# Sheet2.net
KiCad netlist of a schematic drawn in Altium Designer
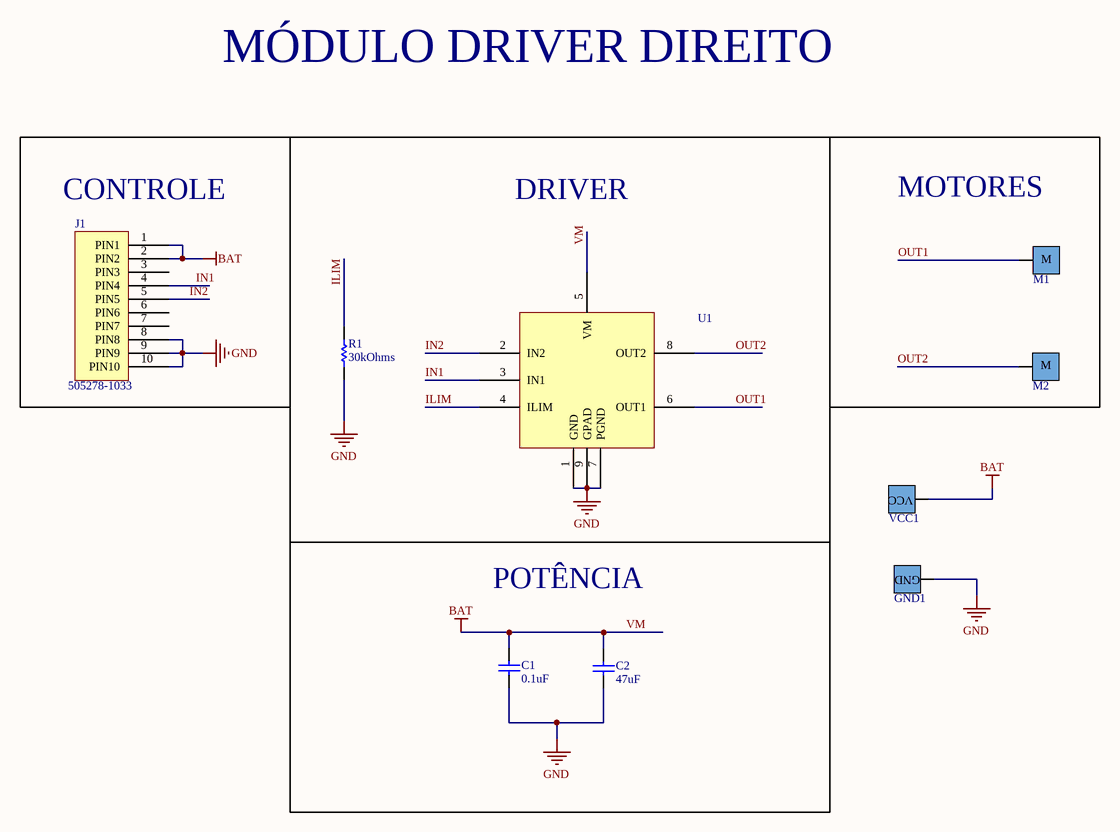
[diagram p0: Sheet2.SchDoc]

(export (version "E")
  (design (tool "Eeschema 10.0.6"))
  (components
    (comp (ref "C1")
      (value "0.1uF")
      (footprint "C0805")
      (description "CAP CER 100nF 25V X7R 0805")
      (fields
        (field (name "MANUFACTURER") "Kemet")
        (field (name "PART NUMBER") "C0805C104M3RACTU")
        (field (name "LIBRARY CONTROL - PERSON THAT CHECKED FOOTPRINT") "Cage")
        (field (name "LIBRARY CONTROL - PERSON THAT CHECKED SCHEMATIC") "Cage")
        (field (name "LIBRARY CONTROL - PERSON THAT DID THE LAST UPDATE FOOTPRINT") "Cage")
        (field (name "LIBRARY CONTROL - PERSON THAT DID THE LAST UPDATE SCHEMATIC") "Cage")
      )
      (libsource (lib "Uai!Tecas") (part "C0805C104M3RACTU"))
    )
    (comp (ref "C2")
      (value "47uF")
      (footprint "C1210")
      (description "CAP CER 47uF 16V X6S 1210")
      (fields
        (field (name "MANUFACTURER") "Murata")
        (field (name "PART NUMBER") "GRM32EC81C476KE15K")
        (field (name "LIBRARY CONTROL - PERSON THAT CHECKED FOOTPRINT") "Cage")
        (field (name "LIBRARY CONTROL - PERSON THAT CHECKED SCHEMATIC") "Cage")
        (field (name "LIBRARY CONTROL - PERSON THAT DID THE LAST UPDATE FOOTPRINT") "Prisma")
        (field (name "LIBRARY CONTROL - PERSON THAT DID THE LAST UPDATE SCHEMATIC") "Prisma")
      )
      (libsource (lib "Capacitor") (part "GRM32EC81C476KE15K"))
    )
    (comp (ref "GND1")
      (value "Ground Pad")
      (footprint "PAD_ALIMENTAÇÃO_MINI")
      (description "GND PAD MINI SUMÔ")
      (libsource (lib "Uai!Tecas") (part "Ground Pad Mini Sumô"))
    )
    (comp (ref "J1")
      (value "505278-1033")
      (footprint "FPC_CON")
      (description "CONN FFC/FPC HORZ 10POS 0.50MM")
      (fields
        (field (name "MANUFACTURER") "Molex")
        (field (name "LIBRARY CONTROL - PERSON THAT CHECKED FOOTPRINT") "Lucas")
        (field (name "LIBRARY CONTROL - PERSON THAT CHECKED SCHEMATIC") "Lucas")
        (field (name "LIBRARY CONTROL - PERSON THAT DID THE LAST UPDATE FOOTPRINT") "Mateus(Dimas)")
        (field (name "LIBRARY CONTROL - PERSON THAT DID THE LAST UPDATE SCHEMATIC") "Mateus(Dimas)")
      )
      (libsource (lib "Uai!Tecas") (part "505278-1033_BODY"))
    )
    (comp (ref "M1")
      (value "Motor Pad")
      (footprint "PAD_MOTOR_MINI")
      (description "MOTOR PAD MINI SUMÔ")
      (libsource (lib "Uai!Tecas") (part "Motor Pad Mini Sumô"))
    )
    (comp (ref "M2")
      (value "Motor Pad")
      (footprint "PAD_MOTOR_MINI")
      (description "MOTOR PAD MINI SUMÔ")
      (libsource (lib "Uai!Tecas") (part "Motor Pad Mini Sumô"))
    )
    (comp (ref "R1")
      (value "30kOhms")
      (footprint "RESC1608X55N")
      (description "RES SMD 30 kOHMS 1% 1/10W 0603")
      (fields
        (field (name "MANUFACTURER") "YAGEO")
        (field (name "PART NUMBER") "RC0603FR-0730KL")
        (field (name "LIBRARY CONTROL - PERSON THAT CHECKED FOOTPRINT") "Guilherme")
        (field (name "LIBRARY CONTROL - PERSON THAT CHECKED SCHEMATIC") "Guilherme")
        (field (name "LIBRARY CONTROL - PERSON THAT DID THE LAST UPDATE FOOTPRINT") "Guilherme")
        (field (name "LIBRARY CONTROL - PERSON THAT DID THE LAST UPDATE SCHEMATIC") "Guilherme")
      )
      (libsource (lib "Uai!Tecas") (part "RC0603FR-0730KL"))
    )
    (comp (ref "U1")
      (value "DRV8871DDA")
      (footprint "SO-PowerPad-8(8_pins)")
      (description "IC MTR DRV (6.5V ~ 45V) (3.5 A) SO-PowerPad-8")
      (fields
        (field (name "MANUFACTURER") "Texas Instruments")
        (field (name "LIBRARY CONTROL - PERSON THAT CHECKED SCHEMATIC") "Stéfany (Ster)")
        (field (name "LIBRARY CONTROL - PERSON THAT CHECKED FOOTPRINT") "Stéfany (Ster)")
        (field (name "LIBRARY CONTROL - PERSON THAT DID THE LAST UPDATE SCHEMATIC") "Stéfany (Ster)")
        (field (name "LIBRARY CONTROL - PERSON THAT DID THE LAST UPDATE FOOTPRINT") "Maria Laura")
      )
      (libsource (lib "Uai!Tecas") (part "DRV8871DDA"))
    )
    (comp (ref "VCC1")
      (value "Source Pad")
      (footprint "PAD_ALIMENTAÇÃO_MINI")
      (description "VCC PAD MINI SUMÔ")
      (libsource (lib "Uai!Tecas") (part "Source Pad Mini Sumô"))
    )
  )
  (nets
    (net (code "1") (name "/ILIM") (class "Default")
      (node (ref "R1") (pin "1") (pinfunction "1_1") (pintype "passive"))
      (node (ref "U1") (pin "4") (pinfunction "ILIM_4") (pintype "passive"))
    )
    (net (code "2") (name "/IN1") (class "Default")
      (node (ref "J1") (pin "4") (pinfunction "PIN4_4") (pintype "passive"))
      (node (ref "U1") (pin "3") (pinfunction "IN1_3") (pintype "passive"))
    )
    (net (code "3") (name "/IN2") (class "Default")
      (node (ref "J1") (pin "5") (pinfunction "PIN5_5") (pintype "passive"))
      (node (ref "U1") (pin "2") (pinfunction "IN2_2") (pintype "passive"))
    )
    (net (code "4") (name "/OUT1") (class "Default")
      (node (ref "M1") (pin "M") (pinfunction "M_M") (pintype "passive"))
      (node (ref "U1") (pin "6") (pinfunction "OUT1_6") (pintype "passive"))
    )
    (net (code "5") (name "/OUT2") (class "Default")
      (node (ref "M2") (pin "M") (pinfunction "M_M") (pintype "passive"))
      (node (ref "U1") (pin "8") (pinfunction "OUT2_8") (pintype "passive"))
    )
    (net (code "6") (name "BAT") (class "Default")
      (node (ref "C1") (pin "2") (pinfunction "2_2") (pintype "passive"))
      (node (ref "C2") (pin "2") (pinfunction "2_2") (pintype "passive"))
      (node (ref "J1") (pin "1") (pinfunction "PIN1_1") (pintype "passive"))
      (node (ref "J1") (pin "2") (pinfunction "PIN2_2") (pintype "passive"))
      (node (ref "U1") (pin "5") (pinfunction "VM_5") (pintype "passive"))
      (node (ref "VCC1") (pin "A") (pinfunction "VCC_A") (pintype "passive"))
    )
    (net (code "7") (name "GND") (class "Default")
      (node (ref "C1") (pin "1") (pinfunction "1_1") (pintype "passive"))
      (node (ref "C2") (pin "1") (pinfunction "1_1") (pintype "passive"))
      (node (ref "GND1") (pin "A") (pinfunction "GND_A") (pintype "passive"))
      (node (ref "J1") (pin "10") (pinfunction "PIN10_10") (pintype "passive"))
      (node (ref "J1") (pin "8") (pinfunction "PIN8_8") (pintype "passive"))
      (node (ref "J1") (pin "9") (pinfunction "PIN9_9") (pintype "passive"))
      (node (ref "R1") (pin "2") (pinfunction "2_2") (pintype "passive"))
      (node (ref "U1") (pin "1") (pinfunction "GND_1") (pintype "passive"))
      (node (ref "U1") (pin "7") (pinfunction "PGND_7") (pintype "passive"))
      (node (ref "U1") (pin "9") (pinfunction "GPAD_9") (pintype "passive"))
    )
    (net (code "8") (name "unconnected-(J1-PIN3-Pad3)") (class "Default")
      (node (ref "J1") (pin "3") (pinfunction "PIN3_3") (pintype "passive"))
    )
    (net (code "9") (name "unconnected-(J1-PIN6-Pad6)") (class "Default")
      (node (ref "J1") (pin "6") (pinfunction "PIN6_6") (pintype "passive"))
    )
    (net (code "10") (name "unconnected-(J1-PIN7-Pad7)") (class "Default")
      (node (ref "J1") (pin "7") (pinfunction "PIN7_7") (pintype "passive"))
    )
  )
)
